# SCH_Weather-sensor_2024-05-18.net
KiCad netlist of a schematic drawn in EasyEDA
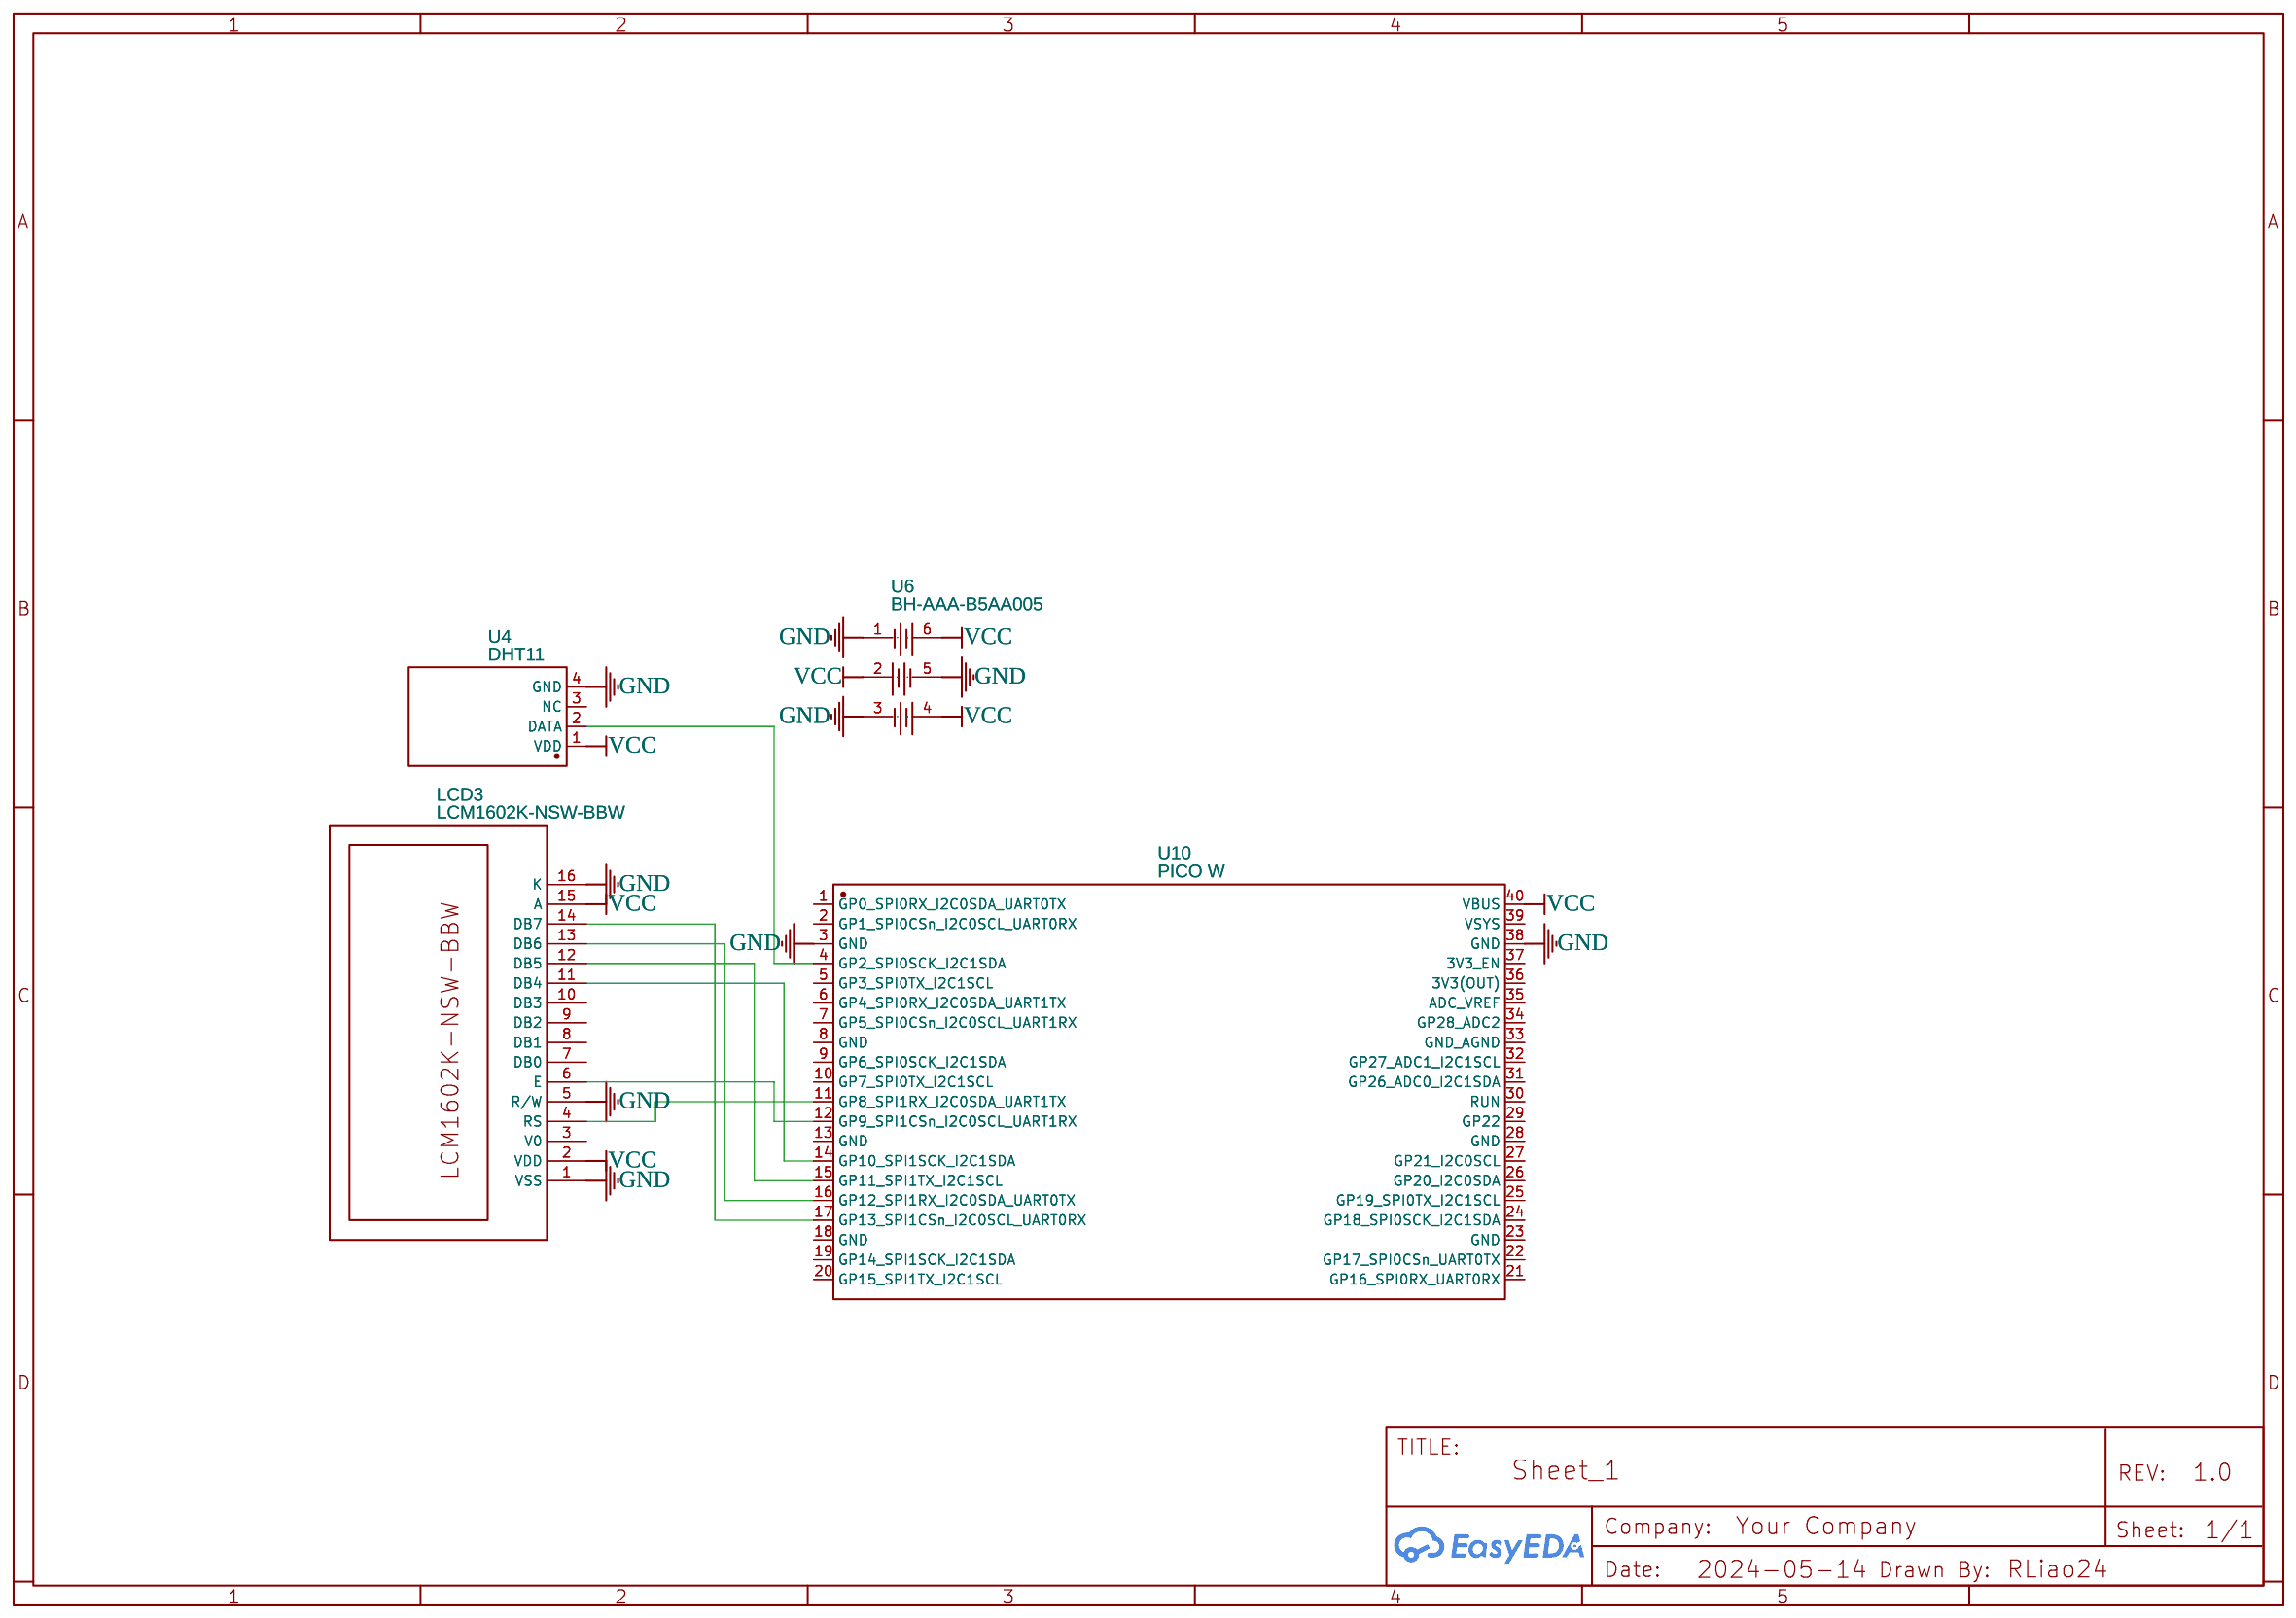
[diagram p0: schematic sheet]

(export (version "E")
  (design (tool "Eeschema 10.0.6"))
  (components
    (comp (ref "LCD3")
      (value "LCM1602K-NSW-BBW")
      (fields (field (name "Manufacturer") "LONTECH(厦门龙特)"))
      (libsource (lib "") (part "LCM1602K-NSW-BBW"))
    )
    (comp (ref "U4")
      (value "DHT11")
      (fields (field (name "Manufacturer") "广州奥松"))
      (libsource (lib "") (part "DHT11"))
    )
    (comp (ref "U6")
      (value "BH-AAA-B5AA005")
      (fields (field (name "Manufacturer") "MYOUNG(美阳)"))
      (libsource (lib "") (part "BH-AAA-B5AA005"))
    )
    (comp (ref "U10")
      (value "PICO W")
      (fields (field (name "Manufacturer") "Raspberry Pi(树莓派)"))
      (libsource (lib "") (part "PICO W"))
    )
  )
  (nets
    (net (code "1") (name "GND") (class "Default")
      (node (ref "LCD3") (pin "1") (pinfunction "VSS_1") (pintype "unspecified"))
      (node (ref "LCD3") (pin "16") (pinfunction "K_16") (pintype "unspecified"))
      (node (ref "LCD3") (pin "5") (pinfunction "R/W_5") (pintype "unspecified"))
      (node (ref "U10") (pin "3") (pinfunction "GND_3") (pintype "unspecified"))
      (node (ref "U10") (pin "38") (pinfunction "GND_38") (pintype "unspecified"))
      (node (ref "U4") (pin "4") (pinfunction "GND_4") (pintype "unspecified"))
      (node (ref "U6") (pin "1") (pinfunction "-_1") (pintype "input"))
      (node (ref "U6") (pin "3") (pinfunction "-_3") (pintype "input"))
      (node (ref "U6") (pin "5") (pinfunction "-_5") (pintype "input"))
    )
    (net (code "2") (name "Net-(LCD3-DB4)") (class "Default")
      (node (ref "LCD3") (pin "11") (pinfunction "DB4_11") (pintype "unspecified"))
      (node (ref "U10") (pin "14") (pinfunction "GP10_SPI1SCK_I2C1SDA_14") (pintype "unspecified"))
    )
    (net (code "3") (name "Net-(LCD3-DB5)") (class "Default")
      (node (ref "LCD3") (pin "12") (pinfunction "DB5_12") (pintype "unspecified"))
      (node (ref "U10") (pin "15") (pinfunction "GP11_SPI1TX_I2C1SCL_15") (pintype "unspecified"))
    )
    (net (code "4") (name "Net-(LCD3-DB6)") (class "Default")
      (node (ref "LCD3") (pin "13") (pinfunction "DB6_13") (pintype "unspecified"))
      (node (ref "U10") (pin "16") (pinfunction "GP12_SPI1RX_I2C0SDA_UART0TX_16") (pintype "unspecified"))
    )
    (net (code "5") (name "Net-(LCD3-DB7)") (class "Default")
      (node (ref "LCD3") (pin "14") (pinfunction "DB7_14") (pintype "unspecified"))
      (node (ref "U10") (pin "17") (pinfunction "GP13_SPI1CSn_I2C0SCL_UART0RX_17") (pintype "unspecified"))
    )
    (net (code "6") (name "Net-(LCD3-E)") (class "Default")
      (node (ref "LCD3") (pin "6") (pinfunction "E_6") (pintype "unspecified"))
      (node (ref "U10") (pin "12") (pinfunction "GP9_SPI1CSn_I2C0SCL_UART1RX_12") (pintype "unspecified"))
    )
    (net (code "7") (name "Net-(LCD3-RS)") (class "Default")
      (node (ref "LCD3") (pin "4") (pinfunction "RS_4") (pintype "unspecified"))
      (node (ref "U10") (pin "11") (pinfunction "GP8_SPI1RX_I2C0SDA_UART1TX_11") (pintype "unspecified"))
    )
    (net (code "8") (name "Net-(U10-GP2_SPI0SCK_I2C1SDA)") (class "Default")
      (node (ref "U10") (pin "4") (pinfunction "GP2_SPI0SCK_I2C1SDA_4") (pintype "unspecified"))
      (node (ref "U4") (pin "2") (pinfunction "DATA_2") (pintype "unspecified"))
    )
    (net (code "9") (name "VCC") (class "Default")
      (node (ref "LCD3") (pin "15") (pinfunction "A_15") (pintype "unspecified"))
      (node (ref "LCD3") (pin "2") (pinfunction "VDD_2") (pintype "unspecified"))
      (node (ref "U10") (pin "40") (pinfunction "VBUS_40") (pintype "unspecified"))
      (node (ref "U4") (pin "1") (pinfunction "VDD_1") (pintype "unspecified"))
      (node (ref "U6") (pin "2") (pinfunction "+_2") (pintype "input"))
      (node (ref "U6") (pin "4") (pinfunction "+_4") (pintype "input"))
      (node (ref "U6") (pin "6") (pinfunction "+_6") (pintype "input"))
    )
    (net (code "10") (name "unconnected-(LCD3-DB0-Pad7)") (class "Default")
      (node (ref "LCD3") (pin "7") (pinfunction "DB0_7") (pintype "unspecified"))
    )
    (net (code "11") (name "unconnected-(LCD3-DB1-Pad8)") (class "Default")
      (node (ref "LCD3") (pin "8") (pinfunction "DB1_8") (pintype "unspecified"))
    )
    (net (code "12") (name "unconnected-(LCD3-DB2-Pad9)") (class "Default")
      (node (ref "LCD3") (pin "9") (pinfunction "DB2_9") (pintype "unspecified"))
    )
    (net (code "13") (name "unconnected-(LCD3-DB3-Pad10)") (class "Default")
      (node (ref "LCD3") (pin "10") (pinfunction "DB3_10") (pintype "unspecified"))
    )
    (net (code "14") (name "unconnected-(LCD3-V0-Pad3)") (class "Default")
      (node (ref "LCD3") (pin "3") (pinfunction "V0_3") (pintype "unspecified"))
    )
    (net (code "15") (name "unconnected-(U4-NC-Pad3)") (class "Default")
      (node (ref "U4") (pin "3") (pinfunction "NC_3") (pintype "unspecified"))
    )
    (net (code "16") (name "unconnected-(U10-3V3(OUT)-Pad36)") (class "Default")
      (node (ref "U10") (pin "36") (pinfunction "3V3(OUT)_36") (pintype "unspecified"))
    )
    (net (code "17") (name "unconnected-(U10-3V3_EN-Pad37)") (class "Default")
      (node (ref "U10") (pin "37") (pinfunction "3V3_EN_37") (pintype "unspecified"))
    )
    (net (code "18") (name "unconnected-(U10-ADC_VREF-Pad35)") (class "Default")
      (node (ref "U10") (pin "35") (pinfunction "ADC_VREF_35") (pintype "unspecified"))
    )
    (net (code "19") (name "unconnected-(U10-GND-Pad8)") (class "Default")
      (node (ref "U10") (pin "8") (pinfunction "GND_8") (pintype "unspecified"))
    )
    (net (code "20") (name "unconnected-(U10-GND-Pad13)") (class "Default")
      (node (ref "U10") (pin "13") (pinfunction "GND_13") (pintype "unspecified"))
    )
    (net (code "21") (name "unconnected-(U10-GND-Pad18)") (class "Default")
      (node (ref "U10") (pin "18") (pinfunction "GND_18") (pintype "unspecified"))
    )
    (net (code "22") (name "unconnected-(U10-GND-Pad23)") (class "Default")
      (node (ref "U10") (pin "23") (pinfunction "GND_23") (pintype "unspecified"))
    )
    (net (code "23") (name "unconnected-(U10-GND-Pad28)") (class "Default")
      (node (ref "U10") (pin "28") (pinfunction "GND_28") (pintype "unspecified"))
    )
    (net (code "24") (name "unconnected-(U10-GND_AGND-Pad33)") (class "Default")
      (node (ref "U10") (pin "33") (pinfunction "GND_AGND_33") (pintype "unspecified"))
    )
    (net (code "25") (name "unconnected-(U10-GP0_SPI0RX_I2C0SDA_UART0TX-Pad1)") (class "Default")
      (node (ref "U10") (pin "1") (pinfunction "GP0_SPI0RX_I2C0SDA_UART0TX_1") (pintype "unspecified"))
    )
    (net (code "26") (name "unconnected-(U10-GP1_SPI0CSn_I2C0SCL_UART0RX-Pad2)") (class "Default")
      (node (ref "U10") (pin "2") (pinfunction "GP1_SPI0CSn_I2C0SCL_UART0RX_2") (pintype "unspecified"))
    )
    (net (code "27") (name "unconnected-(U10-GP3_SPI0TX_I2C1SCL-Pad5)") (class "Default")
      (node (ref "U10") (pin "5") (pinfunction "GP3_SPI0TX_I2C1SCL_5") (pintype "unspecified"))
    )
    (net (code "28") (name "unconnected-(U10-GP4_SPI0RX_I2C0SDA_UART1TX-Pad6)") (class "Default")
      (node (ref "U10") (pin "6") (pinfunction "GP4_SPI0RX_I2C0SDA_UART1TX_6") (pintype "unspecified"))
    )
    (net (code "29") (name "unconnected-(U10-GP5_SPI0CSn_I2C0SCL_UART1RX-Pad7)") (class "Default")
      (node (ref "U10") (pin "7") (pinfunction "GP5_SPI0CSn_I2C0SCL_UART1RX_7") (pintype "unspecified"))
    )
    (net (code "30") (name "unconnected-(U10-GP6_SPI0SCK_I2C1SDA-Pad9)") (class "Default")
      (node (ref "U10") (pin "9") (pinfunction "GP6_SPI0SCK_I2C1SDA_9") (pintype "unspecified"))
    )
    (net (code "31") (name "unconnected-(U10-GP7_SPI0TX_I2C1SCL-Pad10)") (class "Default")
      (node (ref "U10") (pin "10") (pinfunction "GP7_SPI0TX_I2C1SCL_10") (pintype "unspecified"))
    )
    (net (code "32") (name "unconnected-(U10-GP14_SPI1SCK_I2C1SDA-Pad19)") (class "Default")
      (node (ref "U10") (pin "19") (pinfunction "GP14_SPI1SCK_I2C1SDA_19") (pintype "unspecified"))
    )
    (net (code "33") (name "unconnected-(U10-GP15_SPI1TX_I2C1SCL-Pad20)") (class "Default")
      (node (ref "U10") (pin "20") (pinfunction "GP15_SPI1TX_I2C1SCL_20") (pintype "unspecified"))
    )
    (net (code "34") (name "unconnected-(U10-GP16_SPI0RX_UART0RX-Pad21)") (class "Default")
      (node (ref "U10") (pin "21") (pinfunction "GP16_SPI0RX_UART0RX_21") (pintype "unspecified"))
    )
    (net (code "35") (name "unconnected-(U10-GP17_SPI0CSn_UART0TX-Pad22)") (class "Default")
      (node (ref "U10") (pin "22") (pinfunction "GP17_SPI0CSn_UART0TX_22") (pintype "unspecified"))
    )
    (net (code "36") (name "unconnected-(U10-GP18_SPI0SCK_I2C1SDA-Pad24)") (class "Default")
      (node (ref "U10") (pin "24") (pinfunction "GP18_SPI0SCK_I2C1SDA_24") (pintype "unspecified"))
    )
    (net (code "37") (name "unconnected-(U10-GP19_SPI0TX_I2C1SCL-Pad25)") (class "Default")
      (node (ref "U10") (pin "25") (pinfunction "GP19_SPI0TX_I2C1SCL_25") (pintype "unspecified"))
    )
    (net (code "38") (name "unconnected-(U10-GP20_I2C0SDA-Pad26)") (class "Default")
      (node (ref "U10") (pin "26") (pinfunction "GP20_I2C0SDA_26") (pintype "unspecified"))
    )
    (net (code "39") (name "unconnected-(U10-GP21_I2C0SCL-Pad27)") (class "Default")
      (node (ref "U10") (pin "27") (pinfunction "GP21_I2C0SCL_27") (pintype "unspecified"))
    )
    (net (code "40") (name "unconnected-(U10-GP22-Pad29)") (class "Default")
      (node (ref "U10") (pin "29") (pinfunction "GP22_29") (pintype "unspecified"))
    )
    (net (code "41") (name "unconnected-(U10-GP26_ADC0_I2C1SDA-Pad31)") (class "Default")
      (node (ref "U10") (pin "31") (pinfunction "GP26_ADC0_I2C1SDA_31") (pintype "unspecified"))
    )
    (net (code "42") (name "unconnected-(U10-GP27_ADC1_I2C1SCL-Pad32)") (class "Default")
      (node (ref "U10") (pin "32") (pinfunction "GP27_ADC1_I2C1SCL_32") (pintype "unspecified"))
    )
    (net (code "43") (name "unconnected-(U10-GP28_ADC2-Pad34)") (class "Default")
      (node (ref "U10") (pin "34") (pinfunction "GP28_ADC2_34") (pintype "unspecified"))
    )
    (net (code "44") (name "unconnected-(U10-RUN-Pad30)") (class "Default")
      (node (ref "U10") (pin "30") (pinfunction "RUN_30") (pintype "unspecified"))
    )
    (net (code "45") (name "unconnected-(U10-VSYS-Pad39)") (class "Default")
      (node (ref "U10") (pin "39") (pinfunction "VSYS_39") (pintype "unspecified"))
    )
  )
)
